# ext_supply_con.net
KiCad netlist of a schematic drawn in Altium Designer
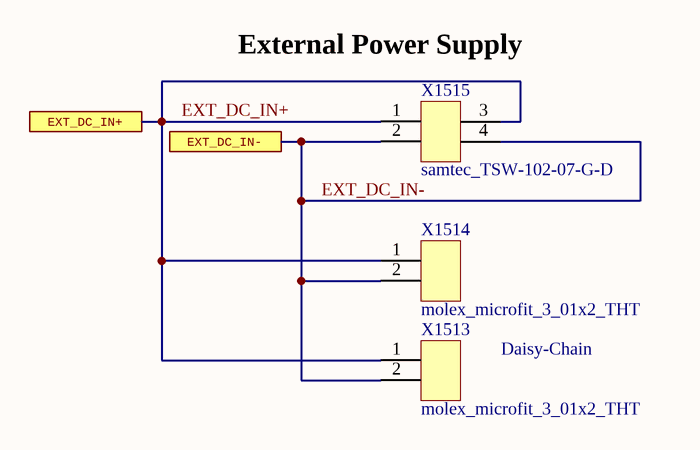
[diagram p0: ext_supply_con.SchDoc]

(export (version "E")
  (design (tool "Eeschema 10.0.6"))
  (components
    (comp (ref "X1513")
      (value "molex_microfit_3_01x2_THT")
      (footprint "MOLEX_MICROFIT_01x2_THT")
      (fields (field (name "MANUFACTURER") "Molex"))
      (libsource (lib "OE750") (part "X2"))
    )
    (comp (ref "X1514")
      (value "molex_microfit_3_01x2_THT")
      (footprint "MOLEX_MICROFIT_01x2_THT")
      (fields (field (name "MANUFACTURER") "Molex"))
      (libsource (lib "OE750") (part "X2"))
    )
    (comp (ref "X1515")
      (value "samtec_TSW-102-07-G-D")
      (footprint "Pinheader_2.54_2x2")
      (description "Board-To-Board Connector, Vertical, 2.54 mm, 4 Contacts, Header, TSW Series, Through Hole, 2 Rows")
      (fields (field (name "MANUFACTURER") "Samtec"))
      (libsource (lib "OE750") (part "X2x2"))
    )
  )
  (nets
    (net (code "1") (name "/EXT_DC_IN+") (class "Default")
      (node (ref "X1513") (pin "1") (pintype "passive"))
      (node (ref "X1514") (pin "1") (pintype "passive"))
      (node (ref "X1515") (pin "1") (pintype "passive"))
      (node (ref "X1515") (pin "3") (pintype "passive"))
    )
    (net (code "2") (name "/EXT_DC_IN-") (class "Default")
      (node (ref "X1513") (pin "2") (pintype "passive"))
      (node (ref "X1514") (pin "2") (pintype "passive"))
      (node (ref "X1515") (pin "2") (pintype "passive"))
      (node (ref "X1515") (pin "4") (pintype "passive"))
    )
  )
)
